# piezo-driver_v0_1-R003.net
KiCad netlist of a schematic drawn in EAGLE
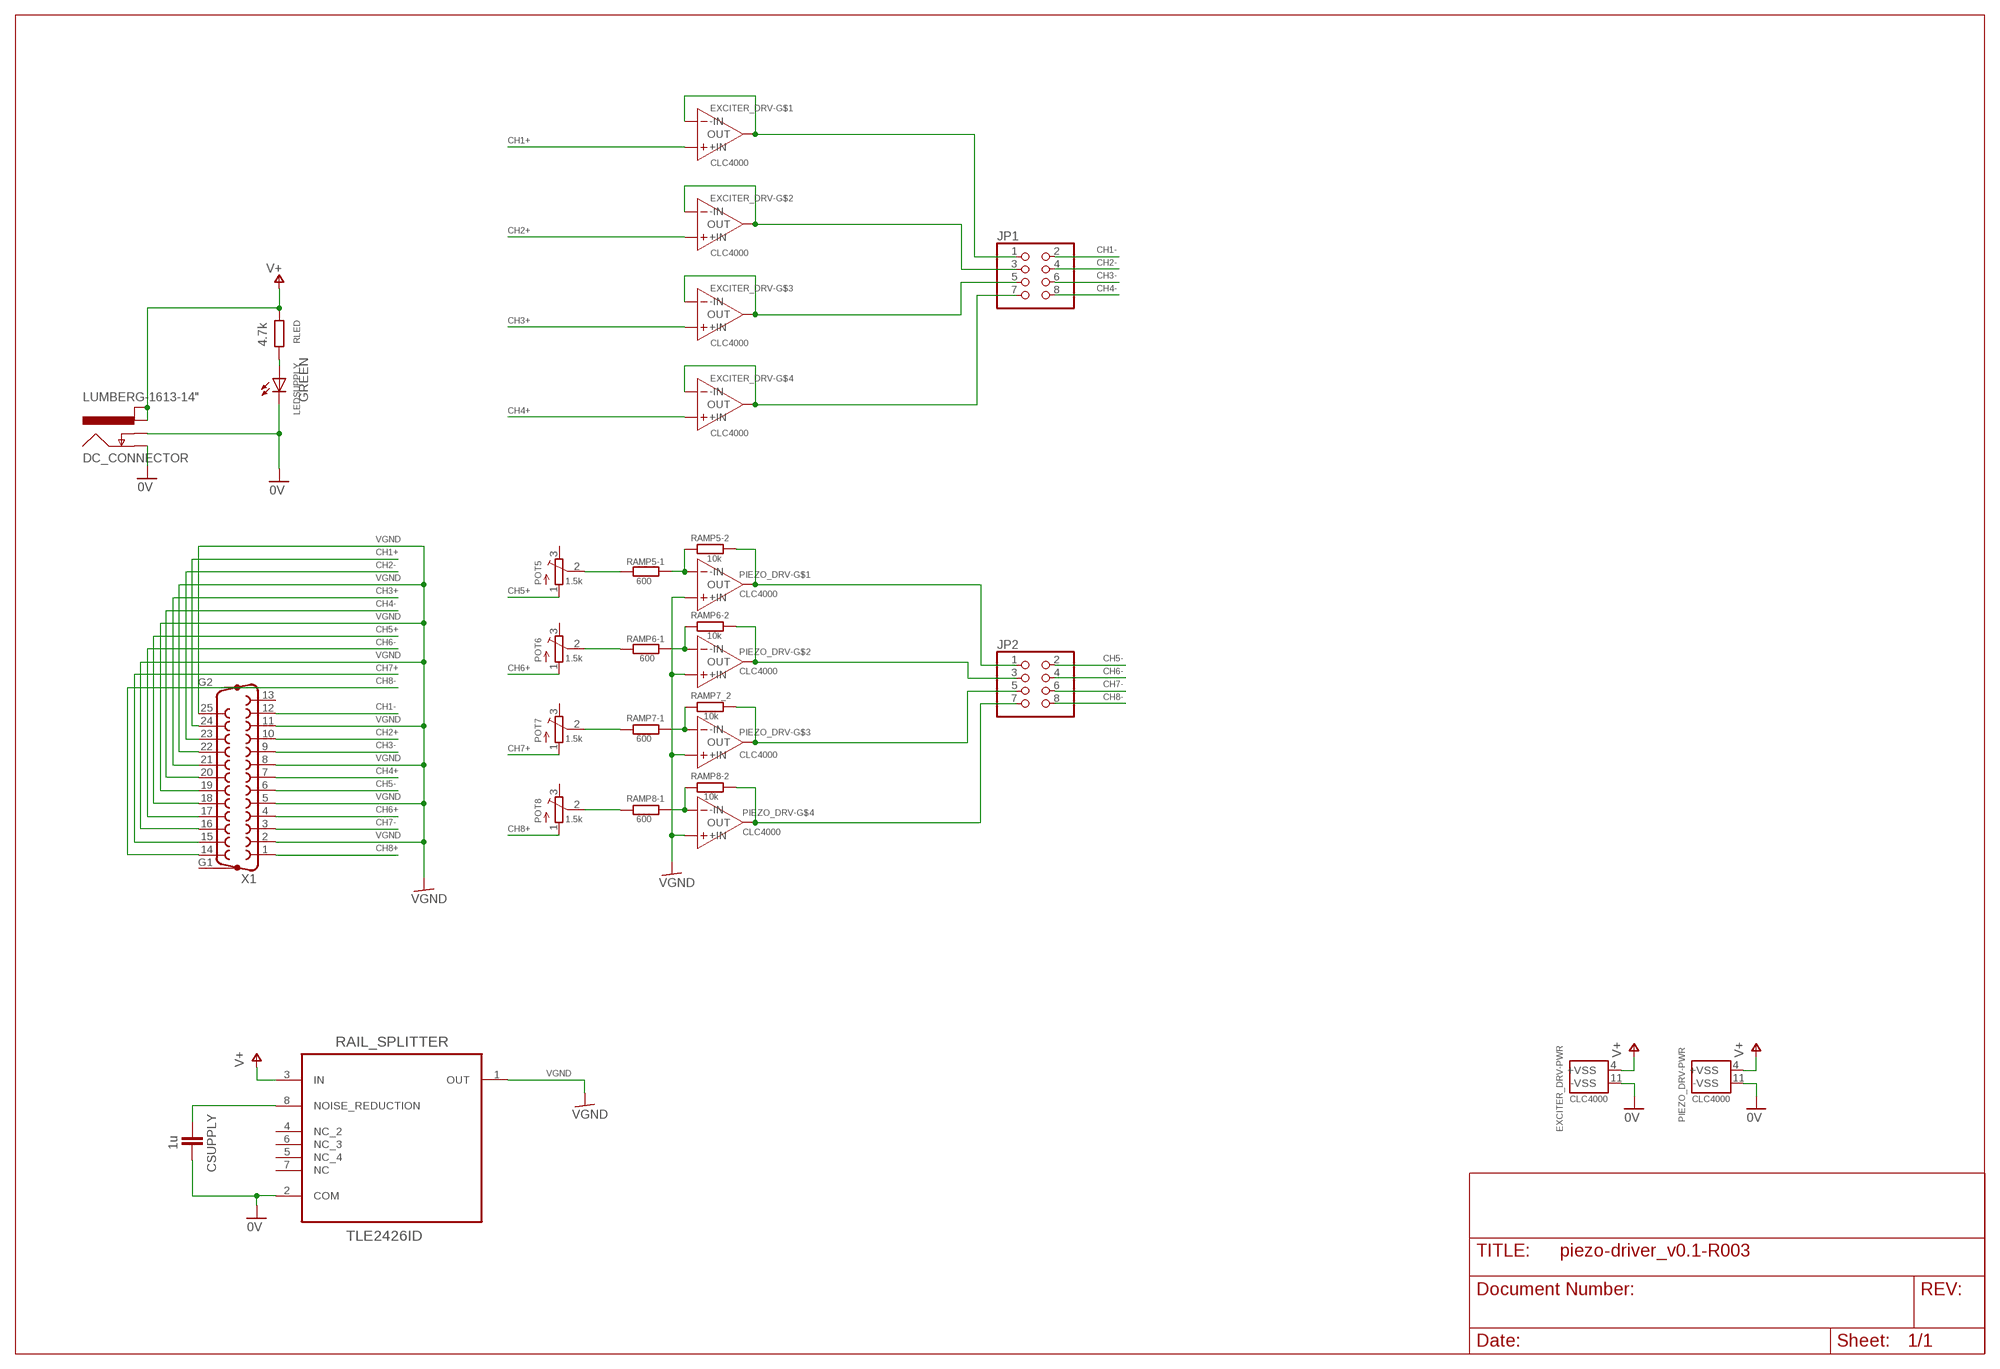
[diagram p0: schematic, sheet 1]

(export (version "E")
  (design (tool "Eeschema 10.0.6"))
  (components
    (comp (ref "CSUPPLY")
      (value "1u")
      (footprint "eagle-import:C0603")
      (libsource (lib "eagle-import") (part "C-EUC0603"))
    )
    (comp (ref "DC_CONNECTOR")
      (value "LUMBERG-1613-14\"")
      (footprint "eagle-import:LUMBERG-1613_14")
      (libsource (lib "eagle-import") (part "LUMBERG-1613-14{dblquote}"))
    )
    (comp (ref "EXCITER_DRV")
      (value "CLC4000")
      (footprint "eagle-import:SOIC-14")
      (libsource (lib "eagle-import") (part "CLC4000"))
    )
    (comp (ref "JP1")
      (value "PINHD-2X4/90")
      (footprint "eagle-import:2X04_90")
      (libsource (lib "eagle-import") (part "PINHD-2X4/90"))
    )
    (comp (ref "JP2")
      (value "PINHD-2X4/90")
      (footprint "eagle-import:2X04_90")
      (libsource (lib "eagle-import") (part "PINHD-2X4/90"))
    )
    (comp (ref "LEDSUPPLY")
      (value "GREEN")
      (footprint "eagle-import:LED3MM")
      (libsource (lib "eagle-import") (part "LED3MM"))
    )
    (comp (ref "PIEZO_DRV")
      (value "CLC4000")
      (footprint "eagle-import:SOIC-14")
      (libsource (lib "eagle-import") (part "CLC4000"))
    )
    (comp (ref "POT5")
      (value "1.5k")
      (footprint "eagle-import:PVG3")
      (libsource (lib "eagle-import") (part "TRIM_EU-PVG3"))
    )
    (comp (ref "POT6")
      (value "1.5k")
      (footprint "eagle-import:PVG3")
      (libsource (lib "eagle-import") (part "TRIM_EU-PVG3"))
    )
    (comp (ref "POT7")
      (value "1.5k")
      (footprint "eagle-import:PVG3")
      (libsource (lib "eagle-import") (part "TRIM_EU-PVG3"))
    )
    (comp (ref "POT8")
      (value "1.5k")
      (footprint "eagle-import:PVG3")
      (libsource (lib "eagle-import") (part "TRIM_EU-PVG3"))
    )
    (comp (ref "RAIL_SPLITTER")
      (value "TLE2426ID")
      (footprint "eagle-import:SOIC127P600X175-8N")
      (libsource (lib "eagle-import") (part "TLE2426ID"))
    )
    (comp (ref "RAMP5-1")
      (value "600")
      (footprint "eagle-import:R0805")
      (libsource (lib "eagle-import") (part "R-EU_R0805"))
    )
    (comp (ref "RAMP5-2")
      (value "10k")
      (footprint "eagle-import:R0805")
      (libsource (lib "eagle-import") (part "R-EU_R0805"))
    )
    (comp (ref "RAMP6-1")
      (value "600")
      (footprint "eagle-import:R0805")
      (libsource (lib "eagle-import") (part "R-EU_R0805"))
    )
    (comp (ref "RAMP6-2")
      (value "10k")
      (footprint "eagle-import:R0805")
      (libsource (lib "eagle-import") (part "R-EU_R0805"))
    )
    (comp (ref "RAMP7-1")
      (value "600")
      (footprint "eagle-import:R0805")
      (libsource (lib "eagle-import") (part "R-EU_R0805"))
    )
    (comp (ref "RAMP7_2")
      (value "10k")
      (footprint "eagle-import:R0805")
      (libsource (lib "eagle-import") (part "R-EU_R0805"))
    )
    (comp (ref "RAMP8-1")
      (value "600")
      (footprint "eagle-import:R0805")
      (libsource (lib "eagle-import") (part "R-EU_R0805"))
    )
    (comp (ref "RAMP8-2")
      (value "10k")
      (footprint "eagle-import:R0805")
      (libsource (lib "eagle-import") (part "R-EU_R0805"))
    )
    (comp (ref "RLED")
      (value "4.7k")
      (footprint "eagle-import:R0805")
      (libsource (lib "eagle-import") (part "R-EU_R0805"))
    )
    (comp (ref "X1")
      (value "F25HP")
      (footprint "eagle-import:F25HP")
      (libsource (lib "eagle-import") (part "F25HP"))
    )
  )
  (nets
    (net (code "1") (name "/CH1+") (class "Default")
      (node (ref "EXCITER_DRV") (pin "3") (pinfunction "+IN_3") (pintype "bidirectional"))
      (node (ref "X1") (pin "24") (pinfunction "24_24") (pintype "passive"))
    )
    (net (code "2") (name "/CH1-") (class "Default")
      (node (ref "JP1") (pin "2") (pinfunction "2_2") (pintype "passive"))
      (node (ref "X1") (pin "12") (pinfunction "12_12") (pintype "passive"))
    )
    (net (code "3") (name "/CH2+") (class "Default")
      (node (ref "EXCITER_DRV") (pin "5") (pinfunction "+IN_5") (pintype "bidirectional"))
      (node (ref "X1") (pin "10") (pinfunction "10_10") (pintype "passive"))
    )
    (net (code "4") (name "/CH2-") (class "Default")
      (node (ref "JP1") (pin "4") (pinfunction "4_4") (pintype "passive"))
      (node (ref "X1") (pin "23") (pinfunction "23_23") (pintype "passive"))
    )
    (net (code "5") (name "/CH3+") (class "Default")
      (node (ref "EXCITER_DRV") (pin "10") (pinfunction "+IN_10") (pintype "bidirectional"))
      (node (ref "X1") (pin "21") (pinfunction "21_21") (pintype "passive"))
    )
    (net (code "6") (name "/CH3-") (class "Default")
      (node (ref "JP1") (pin "6") (pinfunction "6_6") (pintype "passive"))
      (node (ref "X1") (pin "9") (pinfunction "9_9") (pintype "passive"))
    )
    (net (code "7") (name "/CH4+") (class "Default")
      (node (ref "EXCITER_DRV") (pin "12") (pinfunction "+IN_12") (pintype "bidirectional"))
      (node (ref "X1") (pin "7") (pinfunction "7_7") (pintype "passive"))
    )
    (net (code "8") (name "/CH4-") (class "Default")
      (node (ref "JP1") (pin "8") (pinfunction "8_8") (pintype "passive"))
      (node (ref "X1") (pin "20") (pinfunction "20_20") (pintype "passive"))
    )
    (net (code "9") (name "/CH5+") (class "Default")
      (node (ref "POT5") (pin "1") (pinfunction "A_1") (pintype "passive"))
      (node (ref "X1") (pin "18") (pinfunction "18_18") (pintype "passive"))
    )
    (net (code "10") (name "/CH5-") (class "Default")
      (node (ref "JP2") (pin "2") (pinfunction "2_2") (pintype "passive"))
      (node (ref "X1") (pin "6") (pinfunction "6_6") (pintype "passive"))
    )
    (net (code "11") (name "/CH6+") (class "Default")
      (node (ref "POT6") (pin "1") (pinfunction "A_1") (pintype "passive"))
      (node (ref "X1") (pin "4") (pinfunction "4_4") (pintype "passive"))
    )
    (net (code "12") (name "/CH6-") (class "Default")
      (node (ref "JP2") (pin "4") (pinfunction "4_4") (pintype "passive"))
      (node (ref "X1") (pin "17") (pinfunction "17_17") (pintype "passive"))
    )
    (net (code "13") (name "/CH7+") (class "Default")
      (node (ref "POT7") (pin "1") (pinfunction "A_1") (pintype "passive"))
      (node (ref "X1") (pin "15") (pinfunction "15_15") (pintype "passive"))
    )
    (net (code "14") (name "/CH7-") (class "Default")
      (node (ref "JP2") (pin "6") (pinfunction "6_6") (pintype "passive"))
      (node (ref "X1") (pin "3") (pinfunction "3_3") (pintype "passive"))
    )
    (net (code "15") (name "/CH8+") (class "Default")
      (node (ref "POT8") (pin "1") (pinfunction "A_1") (pintype "passive"))
      (node (ref "X1") (pin "1") (pinfunction "1_1") (pintype "passive"))
    )
    (net (code "16") (name "/CH8-") (class "Default")
      (node (ref "JP2") (pin "8") (pinfunction "8_8") (pintype "passive"))
      (node (ref "X1") (pin "14") (pinfunction "14_14") (pintype "passive"))
    )
    (net (code "17") (name "0V") (class "Default")
      (node (ref "CSUPPLY") (pin "2") (pinfunction "2_2") (pintype "passive"))
      (node (ref "DC_CONNECTOR") (pin "1") (pinfunction "GND_1") (pintype "power_in"))
      (node (ref "DC_CONNECTOR") (pin "2") (pinfunction "GND_INS_2") (pintype "power_in"))
      (node (ref "EXCITER_DRV") (pin "11") (pinfunction "-VSS_11") (pintype "power_in"))
      (node (ref "LEDSUPPLY") (pin "K") (pinfunction "C_K") (pintype "passive"))
      (node (ref "PIEZO_DRV") (pin "11") (pinfunction "-VSS_11") (pintype "power_in"))
      (node (ref "RAIL_SPLITTER") (pin "2") (pinfunction "COM_2") (pintype "passive"))
    )
    (net (code "18") (name "Net-(EXCITER_DRVA--IN)") (class "Default")
      (node (ref "EXCITER_DRV") (pin "1") (pinfunction "OUT_1") (pintype "bidirectional"))
      (node (ref "EXCITER_DRV") (pin "2") (pinfunction "-IN_2") (pintype "bidirectional"))
      (node (ref "JP1") (pin "1") (pinfunction "1_1") (pintype "passive"))
    )
    (net (code "19") (name "Net-(EXCITER_DRVB--IN)") (class "Default")
      (node (ref "EXCITER_DRV") (pin "6") (pinfunction "-IN_6") (pintype "bidirectional"))
      (node (ref "EXCITER_DRV") (pin "7") (pinfunction "OUT_7") (pintype "bidirectional"))
      (node (ref "JP1") (pin "3") (pinfunction "3_3") (pintype "passive"))
    )
    (net (code "20") (name "Net-(EXCITER_DRVC--IN)") (class "Default")
      (node (ref "EXCITER_DRV") (pin "8") (pinfunction "OUT_8") (pintype "bidirectional"))
      (node (ref "EXCITER_DRV") (pin "9") (pinfunction "-IN_9") (pintype "bidirectional"))
      (node (ref "JP1") (pin "5") (pinfunction "5_5") (pintype "passive"))
    )
    (net (code "21") (name "Net-(EXCITER_DRVD--IN)") (class "Default")
      (node (ref "EXCITER_DRV") (pin "13") (pinfunction "-IN_13") (pintype "bidirectional"))
      (node (ref "EXCITER_DRV") (pin "14") (pinfunction "OUT_14") (pintype "bidirectional"))
      (node (ref "JP1") (pin "7") (pinfunction "7_7") (pintype "passive"))
    )
    (net (code "22") (name "Net-(LEDSUPPLY-PadA)") (class "Default")
      (node (ref "LEDSUPPLY") (pin "A") (pinfunction "A_A") (pintype "passive"))
      (node (ref "RLED") (pin "1") (pinfunction "1_1") (pintype "passive"))
    )
    (net (code "23") (name "Net-(PIEZO_DRVA--IN)") (class "Default")
      (node (ref "PIEZO_DRV") (pin "2") (pinfunction "-IN_2") (pintype "bidirectional"))
      (node (ref "RAMP5-1") (pin "2") (pinfunction "2_2") (pintype "passive"))
      (node (ref "RAMP5-2") (pin "1") (pinfunction "1_1") (pintype "passive"))
    )
    (net (code "24") (name "Net-(PIEZO_DRVA-OUT)") (class "Default")
      (node (ref "JP2") (pin "1") (pinfunction "1_1") (pintype "passive"))
      (node (ref "PIEZO_DRV") (pin "1") (pinfunction "OUT_1") (pintype "bidirectional"))
      (node (ref "RAMP5-2") (pin "2") (pinfunction "2_2") (pintype "passive"))
    )
    (net (code "25") (name "Net-(PIEZO_DRVB--IN)") (class "Default")
      (node (ref "PIEZO_DRV") (pin "6") (pinfunction "-IN_6") (pintype "bidirectional"))
      (node (ref "RAMP6-1") (pin "2") (pinfunction "2_2") (pintype "passive"))
      (node (ref "RAMP6-2") (pin "1") (pinfunction "1_1") (pintype "passive"))
    )
    (net (code "26") (name "Net-(PIEZO_DRVB-OUT)") (class "Default")
      (node (ref "JP2") (pin "3") (pinfunction "3_3") (pintype "passive"))
      (node (ref "PIEZO_DRV") (pin "7") (pinfunction "OUT_7") (pintype "bidirectional"))
      (node (ref "RAMP6-2") (pin "2") (pinfunction "2_2") (pintype "passive"))
    )
    (net (code "27") (name "Net-(PIEZO_DRVC--IN)") (class "Default")
      (node (ref "PIEZO_DRV") (pin "9") (pinfunction "-IN_9") (pintype "bidirectional"))
      (node (ref "RAMP7-1") (pin "2") (pinfunction "2_2") (pintype "passive"))
      (node (ref "RAMP7_2") (pin "1") (pinfunction "1_1") (pintype "passive"))
    )
    (net (code "28") (name "Net-(PIEZO_DRVC-OUT)") (class "Default")
      (node (ref "JP2") (pin "5") (pinfunction "5_5") (pintype "passive"))
      (node (ref "PIEZO_DRV") (pin "8") (pinfunction "OUT_8") (pintype "bidirectional"))
      (node (ref "RAMP7_2") (pin "2") (pinfunction "2_2") (pintype "passive"))
    )
    (net (code "29") (name "Net-(PIEZO_DRVD--IN)") (class "Default")
      (node (ref "PIEZO_DRV") (pin "13") (pinfunction "-IN_13") (pintype "bidirectional"))
      (node (ref "RAMP8-1") (pin "2") (pinfunction "2_2") (pintype "passive"))
      (node (ref "RAMP8-2") (pin "1") (pinfunction "1_1") (pintype "passive"))
    )
    (net (code "30") (name "Net-(PIEZO_DRVD-OUT)") (class "Default")
      (node (ref "JP2") (pin "7") (pinfunction "7_7") (pintype "passive"))
      (node (ref "PIEZO_DRV") (pin "14") (pinfunction "OUT_14") (pintype "bidirectional"))
      (node (ref "RAMP8-2") (pin "2") (pinfunction "2_2") (pintype "passive"))
    )
    (net (code "31") (name "Net-(POT5-S)") (class "Default")
      (node (ref "POT5") (pin "2") (pinfunction "S_2") (pintype "passive"))
      (node (ref "RAMP5-1") (pin "1") (pinfunction "1_1") (pintype "passive"))
    )
    (net (code "32") (name "Net-(POT6-S)") (class "Default")
      (node (ref "POT6") (pin "2") (pinfunction "S_2") (pintype "passive"))
      (node (ref "RAMP6-1") (pin "1") (pinfunction "1_1") (pintype "passive"))
    )
    (net (code "33") (name "Net-(POT7-S)") (class "Default")
      (node (ref "POT7") (pin "2") (pinfunction "S_2") (pintype "passive"))
      (node (ref "RAMP7-1") (pin "1") (pinfunction "1_1") (pintype "passive"))
    )
    (net (code "34") (name "Net-(POT8-S)") (class "Default")
      (node (ref "POT8") (pin "2") (pinfunction "S_2") (pintype "passive"))
      (node (ref "RAMP8-1") (pin "1") (pinfunction "1_1") (pintype "passive"))
    )
    (net (code "35") (name "Net-(RAIL_SPLITTER-NOISE_REDUCTION)") (class "Default")
      (node (ref "CSUPPLY") (pin "1") (pinfunction "1_1") (pintype "passive"))
      (node (ref "RAIL_SPLITTER") (pin "8") (pinfunction "NOISE_REDUCTION_8") (pintype "passive"))
    )
    (net (code "36") (name "V+") (class "Default")
      (node (ref "DC_CONNECTOR") (pin "3") (pinfunction "PWR_1_3") (pintype "power_in"))
      (node (ref "DC_CONNECTOR") (pin "4") (pinfunction "PWR_2_4") (pintype "power_in"))
      (node (ref "EXCITER_DRV") (pin "4") (pinfunction "+VSS_4") (pintype "power_in"))
      (node (ref "PIEZO_DRV") (pin "4") (pinfunction "+VSS_4") (pintype "power_in"))
      (node (ref "RAIL_SPLITTER") (pin "3") (pinfunction "IN_3") (pintype "input"))
      (node (ref "RLED") (pin "2") (pinfunction "2_2") (pintype "passive"))
    )
    (net (code "37") (name "VGND") (class "Default")
      (node (ref "PIEZO_DRV") (pin "10") (pinfunction "+IN_10") (pintype "bidirectional"))
      (node (ref "PIEZO_DRV") (pin "12") (pinfunction "+IN_12") (pintype "bidirectional"))
      (node (ref "PIEZO_DRV") (pin "3") (pinfunction "+IN_3") (pintype "bidirectional"))
      (node (ref "PIEZO_DRV") (pin "5") (pinfunction "+IN_5") (pintype "bidirectional"))
      (node (ref "RAIL_SPLITTER") (pin "1") (pinfunction "OUT_1") (pintype "output"))
      (node (ref "X1") (pin "11") (pinfunction "11_11") (pintype "passive"))
      (node (ref "X1") (pin "16") (pinfunction "16_16") (pintype "passive"))
      (node (ref "X1") (pin "19") (pinfunction "19_19") (pintype "passive"))
      (node (ref "X1") (pin "2") (pinfunction "2_2") (pintype "passive"))
      (node (ref "X1") (pin "22") (pinfunction "22_22") (pintype "passive"))
      (node (ref "X1") (pin "25") (pinfunction "25_25") (pintype "passive"))
      (node (ref "X1") (pin "5") (pinfunction "5_5") (pintype "passive"))
      (node (ref "X1") (pin "8") (pinfunction "8_8") (pintype "passive"))
    )
    (net (code "38") (name "unconnected-(POT5-E-Pad3)") (class "Default")
      (node (ref "POT5") (pin "3") (pinfunction "E_3") (pintype "passive"))
    )
    (net (code "39") (name "unconnected-(POT6-E-Pad3)") (class "Default")
      (node (ref "POT6") (pin "3") (pinfunction "E_3") (pintype "passive"))
    )
    (net (code "40") (name "unconnected-(POT7-E-Pad3)") (class "Default")
      (node (ref "POT7") (pin "3") (pinfunction "E_3") (pintype "passive"))
    )
    (net (code "41") (name "unconnected-(POT8-E-Pad3)") (class "Default")
      (node (ref "POT8") (pin "3") (pinfunction "E_3") (pintype "passive"))
    )
    (net (code "42") (name "unconnected-(RAIL_SPLITTER-NC-Pad7)") (class "Default")
      (node (ref "RAIL_SPLITTER") (pin "7") (pinfunction "NC_7") (pintype "no_connect"))
    )
    (net (code "43") (name "unconnected-(RAIL_SPLITTER-NC_2-Pad4)") (class "Default")
      (node (ref "RAIL_SPLITTER") (pin "4") (pinfunction "NC_2_4") (pintype "no_connect"))
    )
    (net (code "44") (name "unconnected-(RAIL_SPLITTER-NC_3-Pad6)") (class "Default")
      (node (ref "RAIL_SPLITTER") (pin "6") (pinfunction "NC_3_6") (pintype "no_connect"))
    )
    (net (code "45") (name "unconnected-(RAIL_SPLITTER-NC_4-Pad5)") (class "Default")
      (node (ref "RAIL_SPLITTER") (pin "5") (pinfunction "NC_4_5") (pintype "no_connect"))
    )
    (net (code "46") (name "unconnected-(X1-Pad13)") (class "Default")
      (node (ref "X1") (pin "13") (pinfunction "13_13") (pintype "passive"))
    )
    (net (code "47") (name "unconnected-(X1-PadG1)") (class "Default")
      (node (ref "X1") (pin "G1") (pinfunction "G1_G1") (pintype "passive"))
    )
    (net (code "48") (name "unconnected-(X1-PadG2)") (class "Default")
      (node (ref "X1") (pin "G2") (pinfunction "G2_G2") (pintype "passive"))
    )
  )
)
